# autowater.net
KiCad netlist of a schematic drawn in EAGLE
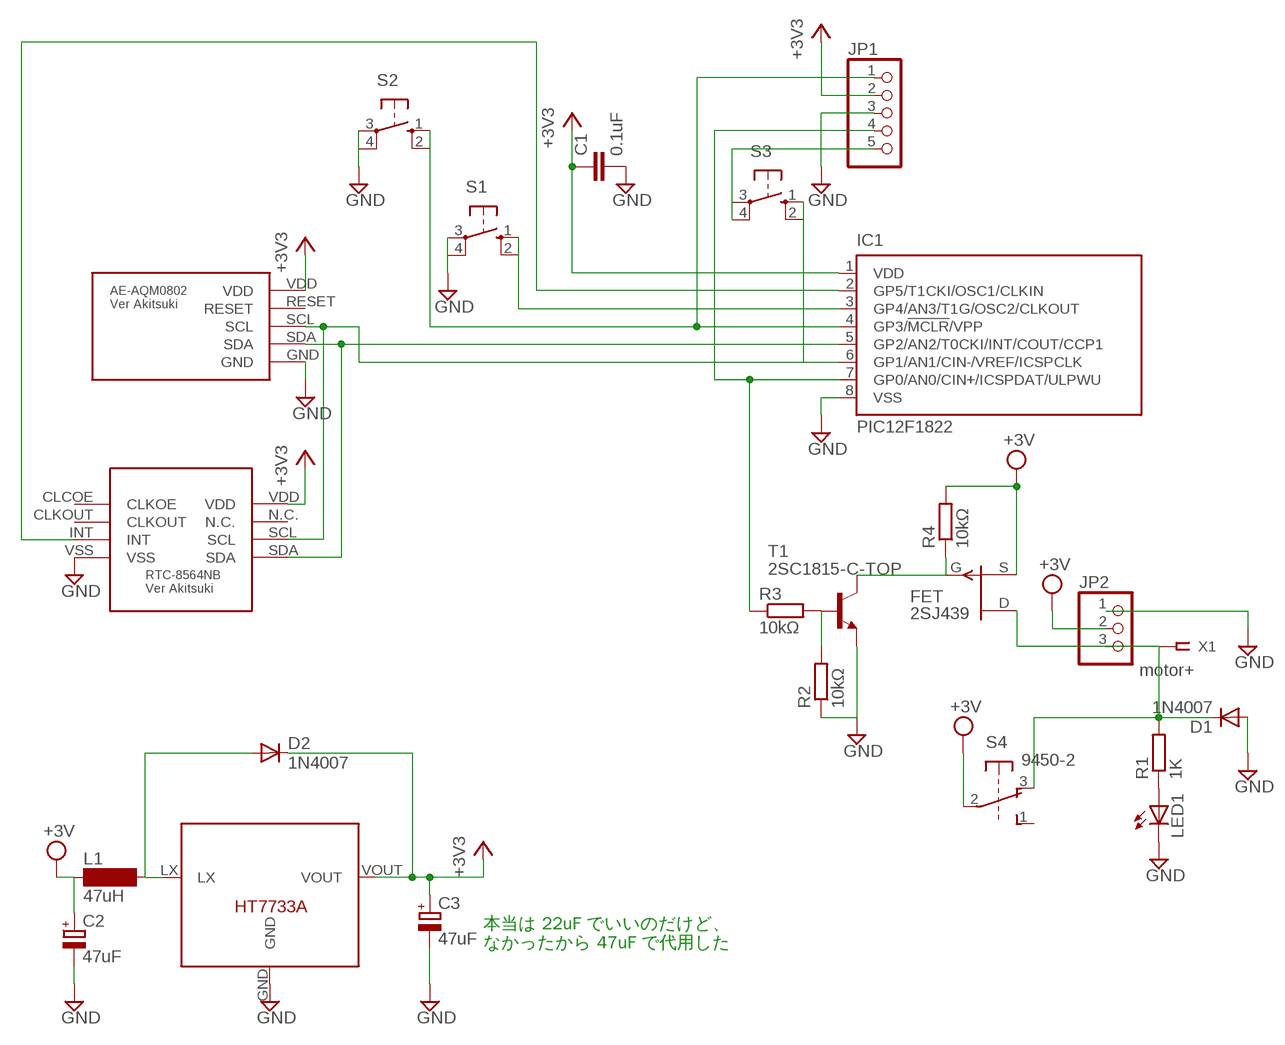
[diagram p0: schematic, sheet 1]

(export (version "E")
  (design (tool "Eeschema 10.0.6"))
  (components
    (comp (ref "C1")
      (value "0.1uF")
      (footprint "eagle-import:C7.5B3")
      (libsource (lib "eagle-import") (part "C7.5/3"))
    )
    (comp (ref "C2")
      (value "47uF")
      (footprint "eagle-import:TT2D5")
      (libsource (lib "eagle-import") (part "CPOL-EUTT2D5"))
    )
    (comp (ref "C3")
      (value "47uF")
      (footprint "eagle-import:TT2D5")
      (libsource (lib "eagle-import") (part "CPOL-EUTT2D5"))
    )
    (comp (ref "D1")
      (value "1N4007")
      (footprint "eagle-import:DO35-7")
      (libsource (lib "eagle-import") (part "1N4148DO35-7"))
    )
    (comp (ref "D2")
      (value "1N4007")
      (footprint "eagle-import:DO35-7")
      (libsource (lib "eagle-import") (part "1N4148DO35-7"))
    )
    (comp (ref "FET")
      (value "2SJ439")
      (footprint "eagle-import:2SJ439")
      (libsource (lib "eagle-import") (part "2SJ439"))
    )
    (comp (ref "IC1")
      (value "PIC12F1822")
      (footprint "eagle-import:DIL8")
      (fields
        (field (name "MF") "MICROCHIP")
        (field (name "MPN") "PIC12F683-I/P")
        (field (name "MPN_1") "PIC12F1822")
      )
      (libsource (lib "eagle-import") (part "PIC12F683P"))
    )
    (comp (ref "JP1")
      (value "PINHD-1X5")
      (footprint "eagle-import:1X05")
      (libsource (lib "eagle-import") (part "PINHD-1X5"))
    )
    (comp (ref "JP2")
      (value "PINHD-1X3")
      (footprint "eagle-import:1X03")
      (libsource (lib "eagle-import") (part "PINHD-1X3"))
    )
    (comp (ref "L1")
      (value "47uH")
      (footprint "eagle-import:SD75")
      (libsource (lib "eagle-import") (part "SD75"))
    )
    (comp (ref "LED1")
      (value "LEDLZR181")
      (footprint "eagle-import:LZR181")
      (libsource (lib "eagle-import") (part "LEDLZR181"))
    )
    (comp (ref "R1")
      (value "1K")
      (footprint "eagle-import:0204_7")
      (libsource (lib "eagle-import") (part "R-EU_0204/7"))
    )
    (comp (ref "R2")
      (value "10kΩ")
      (footprint "eagle-import:0204_7")
      (libsource (lib "eagle-import") (part "R-EU_0204/7"))
    )
    (comp (ref "R3")
      (value "10kΩ")
      (footprint "eagle-import:0207_12")
      (libsource (lib "eagle-import") (part "R-EU_0207/12"))
    )
    (comp (ref "R4")
      (value "10kΩ")
      (footprint "eagle-import:0204_7")
      (libsource (lib "eagle-import") (part "R-EU_0204/7"))
    )
    (comp (ref "S1")
      (value "10-XX")
      (footprint "eagle-import:B3F-10XX")
      (fields
        (field (name "MPN") "B3F-1000")
        (field (name "MPN_1") "B3F-1000")
        (field (name "OC_FARNELL") "176432")
        (field (name "OC_NEWARK") "36M3542")
      )
      (libsource (lib "eagle-import") (part "10-XX"))
    )
    (comp (ref "S2")
      (value "10-XX")
      (footprint "eagle-import:B3F-10XX")
      (fields (field (name "MPN") "B3F-1000"))
      (libsource (lib "eagle-import") (part "10-XX"))
    )
    (comp (ref "S3")
      (value "10-XX")
      (footprint "eagle-import:B3F-10XX")
      (fields
        (field (name "MPN") "B3F-1000")
        (field (name "MPN_1") "B3F-1000")
        (field (name "OC_FARNELL") "176432")
        (field (name "OC_NEWARK") "36M3542")
      )
      (libsource (lib "eagle-import") (part "10-XX"))
    )
    (comp (ref "S4")
      (value "9450-2")
      (footprint "eagle-import:9450-2")
      (libsource (lib "eagle-import") (part "9450-2"))
    )
    (comp (ref "T1")
      (value "2SC1815-C-TOP")
      (footprint "eagle-import:2SC1815-C-TOP")
      (libsource (lib "eagle-import") (part "2SC1815-C-TOP"))
    )
    (comp (ref "U$1")
      (value "RTC-8564NB-VER-AKITSUKI")
      (footprint "eagle-import:RTC-8564NB-VER-AKITSUKI")
      (libsource (lib "eagle-import") (part "RTC-8564NB-VER-AKITSUKI"))
    )
    (comp (ref "U$2")
      (value "AE-AQM0802-VER-AKITSUKI")
      (footprint "eagle-import:AE-AQM0802-VER-AKITSUKI")
      (libsource (lib "eagle-import") (part "AE-AQM0802-VER-AKITSUKI"))
    )
    (comp (ref "U$4")
      (value "HT7733A")
      (footprint "eagle-import:HT7733A")
      (libsource (lib "eagle-import") (part "HT7733A"))
    )
    (comp (ref "X1")
      (value "motor+")
      (footprint "eagle-import:SSW-101-02-S-S")
      (fields (field (name "MPN") "SSW-101-02-S-S"))
      (libsource (lib "eagle-import") (part "SSW-101-02-S-S"))
    )
  )
  (nets
    (net (code "1") (name "+3V") (class "Default")
      (node (ref "C2") (pin "+") (pinfunction "+_+") (pintype "passive"))
      (node (ref "FET") (pin "S") (pinfunction "S_S") (pintype "passive"))
      (node (ref "JP2") (pin "2") (pinfunction "2_2") (pintype "passive"))
      (node (ref "L1") (pin "1") (pinfunction "1_1") (pintype "passive"))
      (node (ref "R4") (pin "2") (pinfunction "2_2") (pintype "passive"))
      (node (ref "S4") (pin "2") (pinfunction "P_2") (pintype "passive"))
    )
    (net (code "2") (name "+3V3") (class "Default")
      (node (ref "C1") (pin "1") (pinfunction "1_1") (pintype "passive"))
      (node (ref "C3") (pin "+") (pinfunction "+_+") (pintype "passive"))
      (node (ref "D2") (pin "C") (pinfunction "C_C") (pintype "passive"))
      (node (ref "IC1") (pin "1") (pinfunction "VDD_1") (pintype "power_in"))
      (node (ref "JP1") (pin "2") (pinfunction "2_2") (pintype "passive"))
      (node (ref "U$1") (pin "VDD") (pinfunction "VDD_VDD") (pintype "bidirectional"))
      (node (ref "U$2") (pin "VDD") (pinfunction "VDD_VDD") (pintype "bidirectional"))
      (node (ref "U$4") (pin "VOUT") (pinfunction "VOUT_VOUT") (pintype "bidirectional"))
    )
    (net (code "3") (name "GND") (class "Default")
      (node (ref "C1") (pin "2") (pinfunction "2_2") (pintype "passive"))
      (node (ref "C2") (pin "-") (pinfunction "-_-") (pintype "passive"))
      (node (ref "C3") (pin "-") (pinfunction "-_-") (pintype "passive"))
      (node (ref "D1") (pin "A") (pinfunction "A_A") (pintype "passive"))
      (node (ref "IC1") (pin "8") (pinfunction "VSS_8") (pintype "power_in"))
      (node (ref "JP1") (pin "3") (pinfunction "3_3") (pintype "passive"))
      (node (ref "JP2") (pin "1") (pinfunction "1_1") (pintype "passive"))
      (node (ref "LED1") (pin "K") (pinfunction "C_K") (pintype "passive"))
      (node (ref "R2") (pin "1") (pinfunction "1_1") (pintype "passive"))
      (node (ref "S1") (pin "3") (pinfunction "P_3") (pintype "passive"))
      (node (ref "S2") (pin "3") (pinfunction "P_3") (pintype "passive"))
      (node (ref "T1") (pin "E") (pinfunction "E_E") (pintype "passive"))
      (node (ref "U$1") (pin "VSS") (pinfunction "VSS_VSS") (pintype "bidirectional"))
      (node (ref "U$2") (pin "GND") (pinfunction "GND_GND") (pintype "bidirectional"))
      (node (ref "U$4") (pin "GND") (pinfunction "GND_GND") (pintype "bidirectional"))
    )
    (net (code "4") (name "Net-(D2-PadA)") (class "Default")
      (node (ref "D2") (pin "A") (pinfunction "A_A") (pintype "passive"))
      (node (ref "L1") (pin "2") (pinfunction "2_2") (pintype "passive"))
      (node (ref "U$4") (pin "LX") (pinfunction "LX_LX") (pintype "bidirectional"))
    )
    (net (code "5") (name "Net-(FET-PadG)") (class "Default")
      (node (ref "FET") (pin "G") (pinfunction "G_G") (pintype "passive"))
      (node (ref "R4") (pin "1") (pinfunction "1_1") (pintype "passive"))
      (node (ref "T1") (pin "C") (pinfunction "C_C") (pintype "passive"))
    )
    (net (code "6") (name "Net-(IC1-GP0{slash}AN0{slash}CIN+{slash}ICSPDAT{slash}ULPWU)") (class "Default")
      (node (ref "IC1") (pin "7") (pinfunction "GP0/AN0/CIN+/ICSPDAT/ULPWU_7") (pintype "bidirectional"))
      (node (ref "JP1") (pin "4") (pinfunction "4_4") (pintype "passive"))
      (node (ref "R3") (pin "1") (pinfunction "1_1") (pintype "passive"))
    )
    (net (code "7") (name "Net-(IC1-GP1{slash}AN1{slash}CIN-{slash}VREF{slash}ICSPCLK)") (class "Default")
      (node (ref "IC1") (pin "6") (pinfunction "GP1/AN1/CIN-/VREF/ICSPCLK_6") (pintype "bidirectional"))
      (node (ref "S3") (pin "1") (pinfunction "S_1") (pintype "passive"))
      (node (ref "U$1") (pin "SCL") (pinfunction "SCL_SCL") (pintype "bidirectional"))
      (node (ref "U$2") (pin "SCL") (pinfunction "SCL_SCL") (pintype "bidirectional"))
    )
    (net (code "8") (name "Net-(IC1-GP2{slash}AN2{slash}T0CKI{slash}INT{slash}COUT{slash}CCP1)") (class "Default")
      (node (ref "IC1") (pin "5") (pinfunction "GP2/AN2/T0CKI/INT/COUT/CCP1_5") (pintype "bidirectional"))
      (node (ref "U$1") (pin "SDA") (pinfunction "SDA_SDA") (pintype "bidirectional"))
      (node (ref "U$2") (pin "SDA") (pinfunction "SDA_SDA") (pintype "bidirectional"))
    )
    (net (code "9") (name "Net-(IC1-GP3{slash}~{MCLR}{slash}VPP)") (class "Default")
      (node (ref "IC1") (pin "4") (pinfunction "GP3/~{MCLR}/VPP_4") (pintype "bidirectional"))
      (node (ref "JP1") (pin "1") (pinfunction "1_1") (pintype "passive"))
      (node (ref "S2") (pin "1") (pinfunction "S_1") (pintype "passive"))
    )
    (net (code "10") (name "Net-(IC1-GP4{slash}AN3{slash}T1G{slash}OSC2{slash}CLKOUT)") (class "Default")
      (node (ref "IC1") (pin "3") (pinfunction "GP4/AN3/T1G/OSC2/CLKOUT_3") (pintype "bidirectional"))
      (node (ref "S1") (pin "1") (pinfunction "S_1") (pintype "passive"))
    )
    (net (code "11") (name "Net-(IC1-GP5{slash}T1CKI{slash}OSC1{slash}CLKIN)") (class "Default")
      (node (ref "IC1") (pin "2") (pinfunction "GP5/T1CKI/OSC1/CLKIN_2") (pintype "bidirectional"))
      (node (ref "U$1") (pin "INT") (pinfunction "INT_INT") (pintype "bidirectional"))
    )
    (net (code "12") (name "Net-(LED1-PadA)") (class "Default")
      (node (ref "LED1") (pin "A") (pinfunction "A_A") (pintype "passive"))
      (node (ref "R1") (pin "1") (pinfunction "1_1") (pintype "passive"))
    )
    (net (code "13") (name "Net-(R2-Pad2)") (class "Default")
      (node (ref "R2") (pin "2") (pinfunction "2_2") (pintype "passive"))
      (node (ref "R3") (pin "2") (pinfunction "2_2") (pintype "passive"))
      (node (ref "T1") (pin "B") (pinfunction "B_B") (pintype "passive"))
    )
    (net (code "14") (name "Net-(S3-P1)") (class "Default")
      (node (ref "JP1") (pin "5") (pinfunction "5_5") (pintype "passive"))
      (node (ref "S3") (pin "4") (pinfunction "P1_4") (pintype "passive"))
    )
    (net (code "15") (name "Net-(S4A-O)") (class "Default")
      (node (ref "D1") (pin "C") (pinfunction "C_C") (pintype "passive"))
      (node (ref "FET") (pin "D") (pinfunction "D_D") (pintype "passive"))
      (node (ref "JP2") (pin "3") (pinfunction "3_3") (pintype "passive"))
      (node (ref "R1") (pin "2") (pinfunction "2_2") (pintype "passive"))
      (node (ref "S4") (pin "3") (pinfunction "O_3") (pintype "passive"))
      (node (ref "X1") (pin "1") (pinfunction "1_1") (pintype "passive"))
    )
    (net (code "16") (name "unconnected-(S1-P1-Pad4)") (class "Default")
      (node (ref "S1") (pin "4") (pinfunction "P1_4") (pintype "passive"))
    )
    (net (code "17") (name "unconnected-(S1-S1-Pad2)") (class "Default")
      (node (ref "S1") (pin "2") (pinfunction "S1_2") (pintype "passive"))
    )
    (net (code "18") (name "unconnected-(S2-P1-Pad4)") (class "Default")
      (node (ref "S2") (pin "4") (pinfunction "P1_4") (pintype "passive"))
    )
    (net (code "19") (name "unconnected-(S2-S1-Pad2)") (class "Default")
      (node (ref "S2") (pin "2") (pinfunction "S1_2") (pintype "passive"))
    )
    (net (code "20") (name "unconnected-(S3-P-Pad3)") (class "Default")
      (node (ref "S3") (pin "3") (pinfunction "P_3") (pintype "passive"))
    )
    (net (code "21") (name "unconnected-(S3-S1-Pad2)") (class "Default")
      (node (ref "S3") (pin "2") (pinfunction "S1_2") (pintype "passive"))
    )
    (net (code "22") (name "unconnected-(S4A-S-Pad1)") (class "Default")
      (node (ref "S4") (pin "1") (pinfunction "S_1") (pintype "passive"))
    )
    (net (code "23") (name "unconnected-(U$1-CLKOE-PadCLCOE)") (class "Default")
      (node (ref "U$1") (pin "CLCOE") (pinfunction "CLKOE_CLCOE") (pintype "bidirectional"))
    )
    (net (code "24") (name "unconnected-(U$1-PadCLKOUT)") (class "Default")
      (node (ref "U$1") (pin "CLKOUT") (pinfunction "CLKOUT_CLKOUT") (pintype "bidirectional"))
    )
    (net (code "25") (name "unconnected-(U$1-PadN.C.)") (class "Default")
      (node (ref "U$1") (pin "N.C.") (pinfunction "N.C._N.C.") (pintype "bidirectional"))
    )
    (net (code "26") (name "unconnected-(U$2-PadRESET)") (class "Default")
      (node (ref "U$2") (pin "RESET") (pinfunction "RESET_RESET") (pintype "bidirectional"))
    )
  )
)
